# Sheet1.net
KiCad netlist of a schematic drawn in Altium Designer
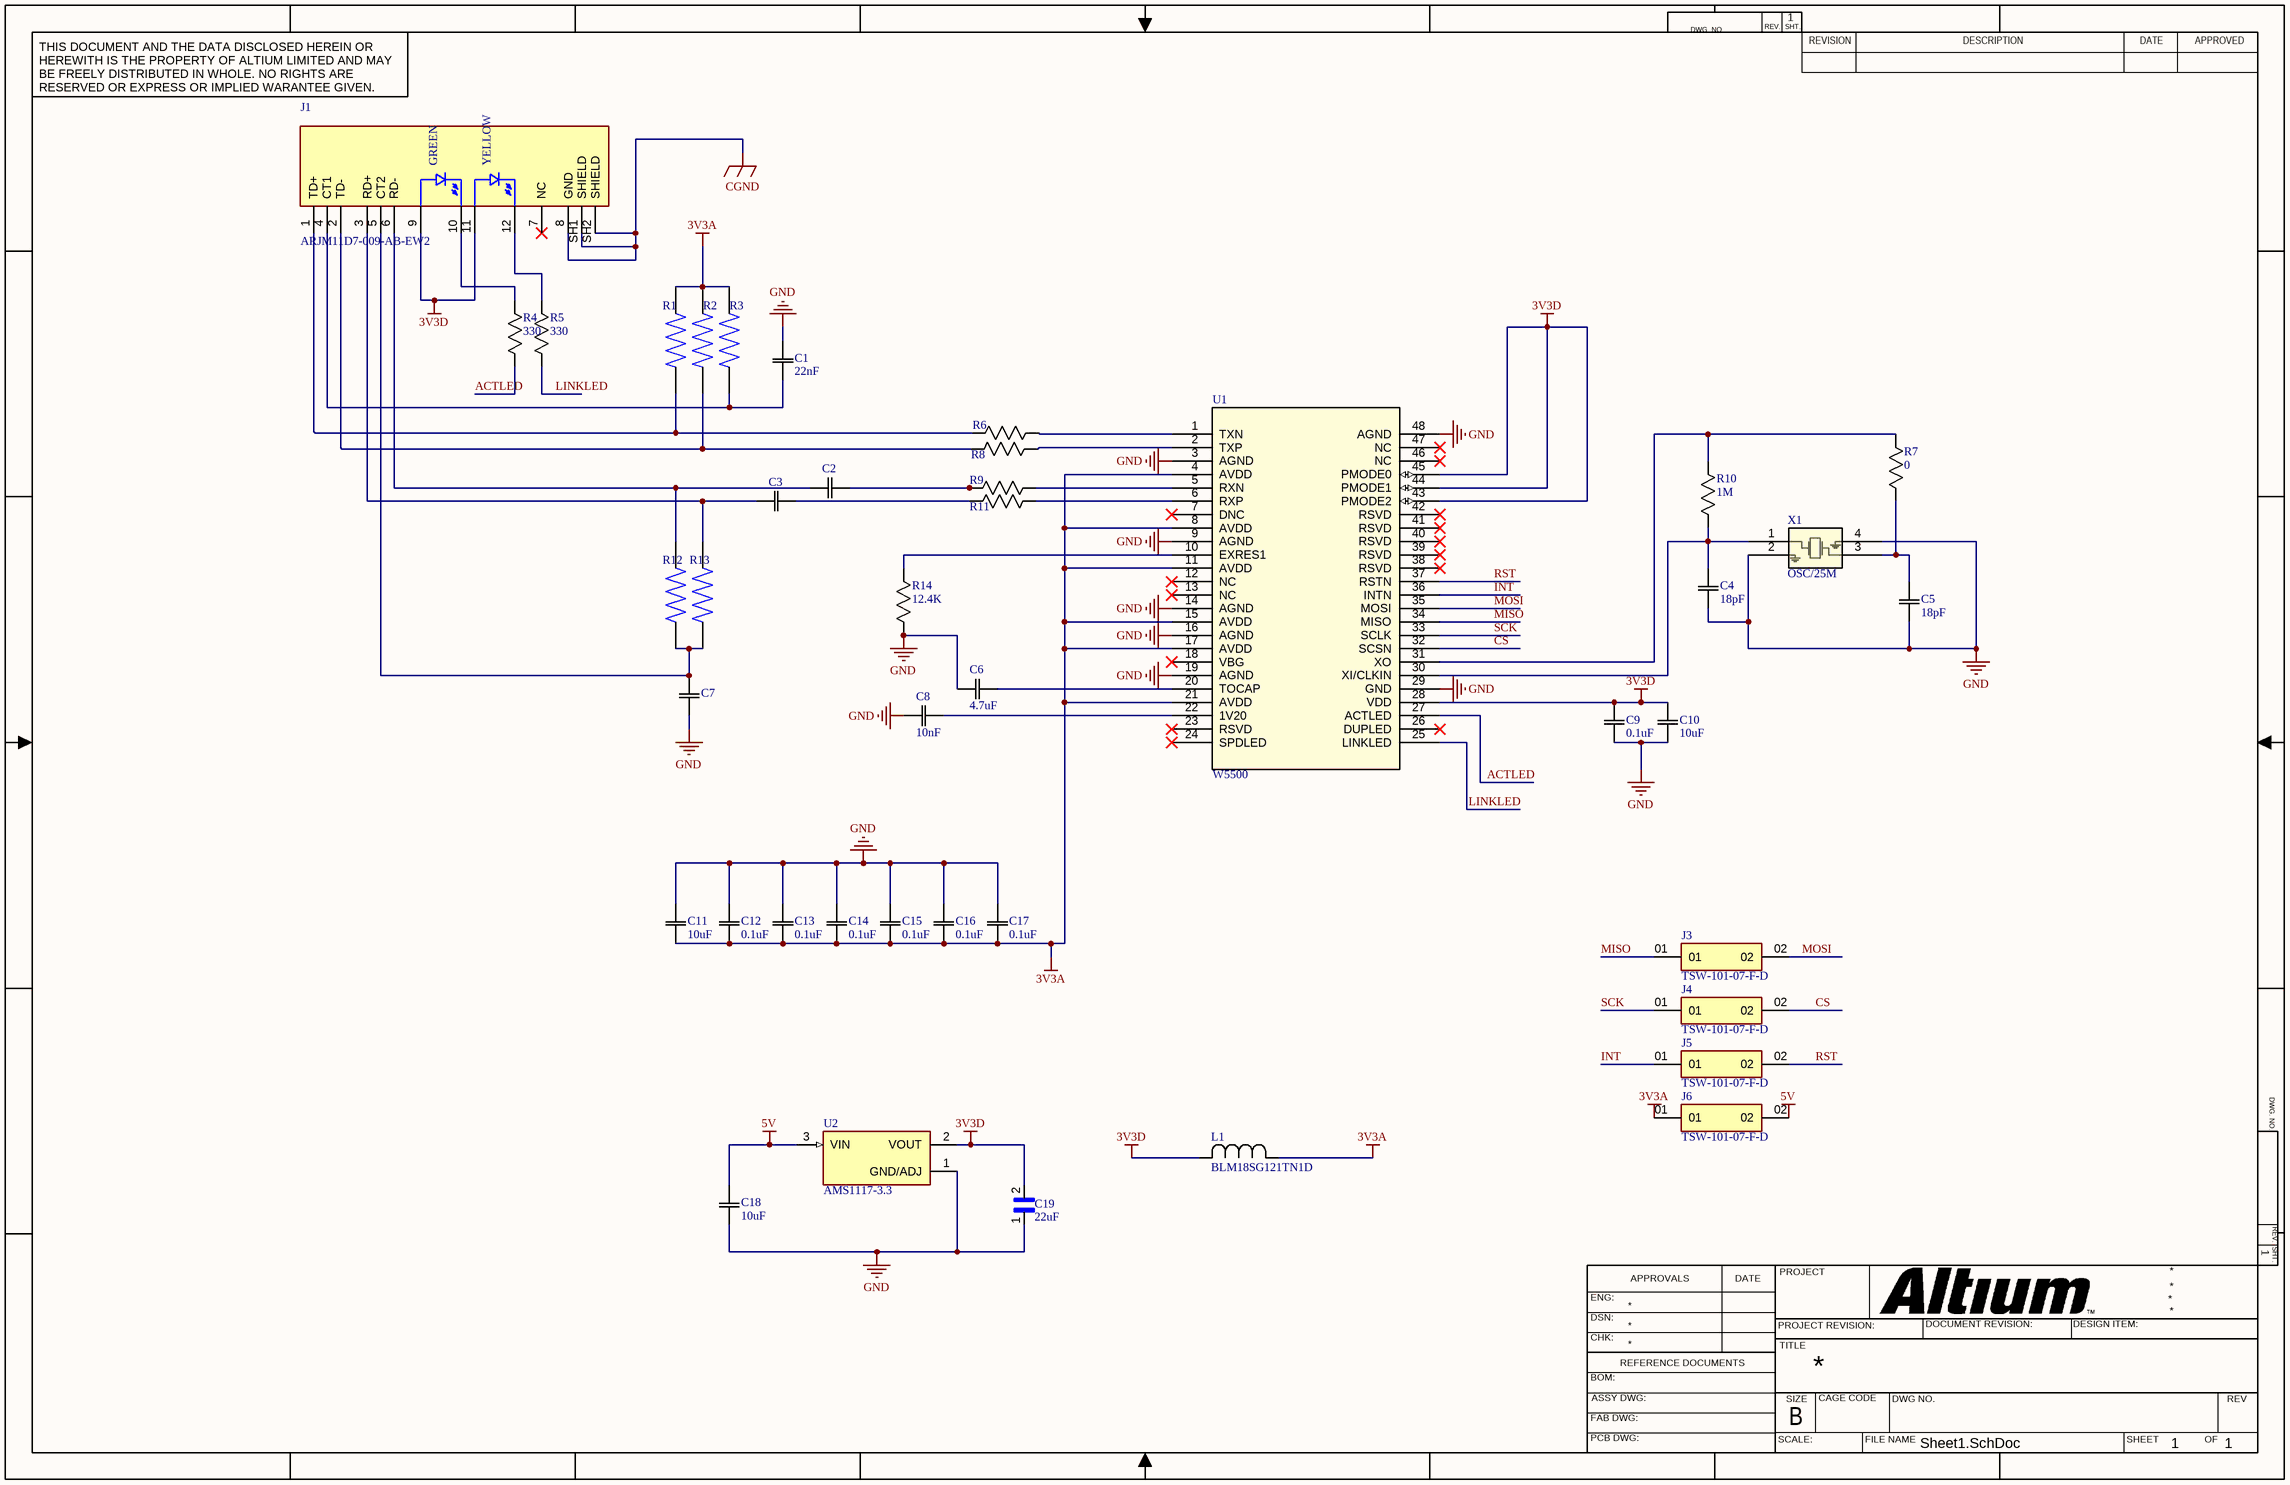
[diagram p0: Sheet1.SchDoc]

(export (version "E")
  (design (tool "Eeschema 10.0.6"))
  (components
    (comp (ref "C1")
      (value "22nF")
      (footprint "CAP_2012_TDK")
      (description "No Description Available")
      (libsource (lib "CAP_22nfar_805pkg") (part "CAP_22nfar_805pkg"))
    )
    (comp (ref "C2")
      (value "CAP_6.8nfar_805pkg")
      (footprint "CC0805N_YAG")
      (description "No Description Available")
      (libsource (lib "CAP_6.8nfar_805pkg") (part "CAP_6.8nfar_805pkg"))
    )
    (comp (ref "C3")
      (value "CAP_6.8nfar_805pkg")
      (footprint "CC0805N_YAG")
      (description "No Description Available")
      (libsource (lib "CAP_6.8nfar_805pkg") (part "CAP_6.8nfar_805pkg"))
    )
    (comp (ref "C4")
      (value "18pF")
      (footprint "CAP_CC0805_YAG")
      (description "No Description Available")
      (libsource (lib "CAP_18pfar_805pkg") (part "CAP_18pfar_805pkg"))
    )
    (comp (ref "C5")
      (value "18pF")
      (footprint "CAP_CC0805_YAG")
      (description "No Description Available")
      (libsource (lib "CAP_18pfar_805pkg") (part "CAP_18pfar_805pkg"))
    )
    (comp (ref "C6")
      (value "4.7uF")
      (footprint "CAP_CL21_SAM")
      (description "No Description Available")
      (libsource (lib "CAP_4.7ufar_805pkg") (part "CAP_4.7ufar_805pkg"))
    )
    (comp (ref "C7")
      (value "CAP_10nfar_805pkg")
      (footprint "CAP_CL21_SAM")
      (description "No Description Available")
      (libsource (lib "CAP_10nfar_805pkg") (part "CAP_10nfar_805pkg"))
    )
    (comp (ref "C8")
      (value "10nF")
      (footprint "CAP_CL21_SAM")
      (description "No Description Available")
      (libsource (lib "CAP_10nfar_805pkg") (part "CAP_10nfar_805pkg"))
    )
    (comp (ref "C9")
      (value "0.1uF")
      (footprint "CC0805N_YAG")
      (description "No Description Available")
      (libsource (lib "CAP_0.1ufar_805pkg") (part "CAP_0.1ufar_805pkg"))
    )
    (comp (ref "C10")
      (value "10uF")
      (footprint "CAP_CL21_SAM")
      (description "No Description Available")
      (libsource (lib "CAP_10ufar_805pkg") (part "CAP_10ufar_805pkg"))
    )
    (comp (ref "C11")
      (value "10uF")
      (footprint "CAP_CL21_SAM")
      (description "No Description Available")
      (libsource (lib "CAP_10ufar_805pkg") (part "CAP_10ufar_805pkg"))
    )
    (comp (ref "C12")
      (value "0.1uF")
      (footprint "CC0805N_YAG")
      (description "No Description Available")
      (libsource (lib "CAP_0.1ufar_805pkg") (part "CAP_0.1ufar_805pkg"))
    )
    (comp (ref "C13")
      (value "0.1uF")
      (footprint "CC0805N_YAG")
      (description "No Description Available")
      (libsource (lib "CAP_0.1ufar_805pkg") (part "CAP_0.1ufar_805pkg"))
    )
    (comp (ref "C14")
      (value "0.1uF")
      (footprint "CC0805N_YAG")
      (description "No Description Available")
      (libsource (lib "CAP_0.1ufar_805pkg") (part "CAP_0.1ufar_805pkg"))
    )
    (comp (ref "C15")
      (value "0.1uF")
      (footprint "CC0805N_YAG")
      (description "No Description Available")
      (libsource (lib "CAP_0.1ufar_805pkg") (part "CAP_0.1ufar_805pkg"))
    )
    (comp (ref "C16")
      (value "0.1uF")
      (footprint "CC0805N_YAG")
      (description "No Description Available")
      (libsource (lib "CAP_0.1ufar_805pkg") (part "CAP_0.1ufar_805pkg"))
    )
    (comp (ref "C17")
      (value "0.1uF")
      (footprint "CC0805N_YAG")
      (description "No Description Available")
      (libsource (lib "CAP_0.1ufar_805pkg") (part "CAP_0.1ufar_805pkg"))
    )
    (comp (ref "C18")
      (value "10uF")
      (footprint "CAP_CL21_SAM")
      (description "No Description Available")
      (libsource (lib "CAP_10ufar_805pkg") (part "CAP_10ufar_805pkg"))
    )
    (comp (ref "C19")
      (value "22uF")
      (footprint "CAPC3225X280N")
      (description "SMD Capacitor X7R_EIA_ with Capacitance: 22uF Tol. 10%. Rated Voltage: 16Vdc")
      (fields (field (name "MP") "GCJ32ER71C226KE01L") (field (name "MF") "Murata"))
      (libsource (lib "CAP_22ufar_1210pkg") (part "GCJ32ER71C226KE01L"))
    )
    (comp (ref "J1")
      (value "ARJM11D7-009-AB-EW2")
      (footprint "ABRACON_ARJM11D7-009-AB-EW2")
      (fields (field (name "MF") "{'manufacturer': u'Abracon LLC'}"))
      (libsource (lib "ARJM11D7-009-AB-EW2") (part "ARJM11D7-009-AB-EW2"))
    )
    (comp (ref "J3")
      (value "TSW-101-07-F-D")
      (footprint "SAMTEC_TSW-101-07-F-D:SAMTEC_TSW-101-07-F-D")
      (fields (field (name "MF") "Samtec"))
      (libsource (lib "TSW-101-07-F-D") (part "TSW-101-07-F-D"))
    )
    (comp (ref "J4")
      (value "TSW-101-07-F-D")
      (footprint "SAMTEC_TSW-101-07-F-D:SAMTEC_TSW-101-07-F-D")
      (fields (field (name "MF") "Samtec"))
      (libsource (lib "TSW-101-07-F-D") (part "TSW-101-07-F-D"))
    )
    (comp (ref "J5")
      (value "TSW-101-07-F-D")
      (footprint "SAMTEC_TSW-101-07-F-D:SAMTEC_TSW-101-07-F-D")
      (fields (field (name "MF") "Samtec"))
      (libsource (lib "TSW-101-07-F-D") (part "TSW-101-07-F-D"))
    )
    (comp (ref "J6")
      (value "TSW-101-07-F-D")
      (footprint "SAMTEC_TSW-101-07-F-D:SAMTEC_TSW-101-07-F-D")
      (fields (field (name "MF") "Samtec"))
      (libsource (lib "TSW-101-07-F-D") (part "TSW-101-07-F-D"))
    )
    (comp (ref "L1")
      (value "BLM18SG121TN1D")
      (footprint "IND_BLM18_0603_MUR")
      (description "No Description Available")
      (libsource (lib "BLM18SG121TN1D") (part "BLM18SG121TN1D"))
    )
    (comp (ref "R1")
      (value "RES_49.9ohm_805pkg")
      (footprint "RESC2012X60N")
      (description "49.9 Ohms Â±1% 0.125W, 1/8W Chip Resistor 0805 _2012 Metric_ Thick Film")
      (fields (field (name "MP") "CRCW080549R9FKEAC") (field (name "MF") "Vishay"))
      (libsource (lib "RES_49.9ohm_806pkg") (part "RES_49.9ohm_805pkg"))
    )
    (comp (ref "R2")
      (value "RES_49.9ohm_805pkg")
      (footprint "RESC2012X60N")
      (description "49.9 Ohms Â±1% 0.125W, 1/8W Chip Resistor 0805 _2012 Metric_ Thick Film")
      (fields (field (name "MP") "CRCW080549R9FKEAC") (field (name "MF") "Vishay"))
      (libsource (lib "RES_49.9ohm_806pkg") (part "RES_49.9ohm_805pkg"))
    )
    (comp (ref "R3")
      (value "RES_49.9ohm_805pkg")
      (footprint "RESC2012X60N")
      (description "49.9 Ohms Â±1% 0.125W, 1/8W Chip Resistor 0805 _2012 Metric_ Thick Film")
      (fields (field (name "MP") "CRCW080549R9FKEAC") (field (name "MF") "Vishay"))
      (libsource (lib "RES_49.9ohm_806pkg") (part "RES_49.9ohm_805pkg"))
    )
    (comp (ref "R4")
      (value "330")
      (footprint "RES_CRCW_0805_VIS")
      (description "No Description Available")
      (libsource (lib "RES_330ohm_805pkg") (part "RES_330ohm_805pkg"))
    )
    (comp (ref "R5")
      (value "330")
      (footprint "RES_CRCW_0805_VIS")
      (description "No Description Available")
      (libsource (lib "RES_330ohm_805pkg") (part "RES_330ohm_805pkg"))
    )
    (comp (ref "R6")
      (value "RES_0ohm_805pkg")
      (footprint "RES_CRCW_0805_VIS")
      (description "No Description Available")
      (libsource (lib "RES_0ohm_805pkg") (part "RES_0ohm_805pkg"))
    )
    (comp (ref "R7")
      (value "0")
      (footprint "RES_CRCW_0805_VIS")
      (description "No Description Available")
      (libsource (lib "RES_0ohm_805pkg") (part "RES_0ohm_805pkg"))
    )
    (comp (ref "R8")
      (value "RES_0ohm_805pkg")
      (footprint "RES_CRCW_0805_VIS")
      (description "No Description Available")
      (libsource (lib "RES_0ohm_805pkg") (part "RES_0ohm_805pkg"))
    )
    (comp (ref "R9")
      (value "RES_0ohm_805pkg")
      (footprint "RES_CRCW_0805_VIS")
      (description "No Description Available")
      (libsource (lib "RES_0ohm_805pkg") (part "RES_0ohm_805pkg"))
    )
    (comp (ref "R10")
      (value "1M")
      (footprint "RES_CRCW_0805")
      (description "No Description Available")
      (libsource (lib "RES_1Mohm_805pkg") (part "RES_1Mohm_805pkg"))
    )
    (comp (ref "R11")
      (value "RES_0ohm_805pkg")
      (footprint "RES_CRCW_0805_VIS")
      (description "No Description Available")
      (libsource (lib "RES_0ohm_805pkg") (part "RES_0ohm_805pkg"))
    )
    (comp (ref "R12")
      (value "RES_49.9ohm_805pkg")
      (footprint "RESC2012X60N")
      (description "49.9 Ohms Â±1% 0.125W, 1/8W Chip Resistor 0805 _2012 Metric_ Thick Film")
      (fields (field (name "MP") "CRCW080549R9FKEAC") (field (name "MF") "Vishay"))
      (libsource (lib "RES_49.9ohm_806pkg") (part "RES_49.9ohm_805pkg"))
    )
    (comp (ref "R13")
      (value "RES_49.9ohm_805pkg")
      (footprint "RESC2012X60N")
      (description "49.9 Ohms Â±1% 0.125W, 1/8W Chip Resistor 0805 _2012 Metric_ Thick Film")
      (fields (field (name "MP") "CRCW080549R9FKEAC") (field (name "MF") "Vishay"))
      (libsource (lib "RES_49.9ohm_806pkg") (part "RES_49.9ohm_805pkg"))
    )
    (comp (ref "R14")
      (value "12.4K")
      (footprint "RES_CRCW_0805")
      (description "No Description Available")
      (libsource (lib "RES_12.4Kohm_805pkg") (part "RES_12.4Kohm_805pkg"))
    )
    (comp (ref "U1")
      (value "W5500")
      (footprint "48LQFP_W5500_WIZ")
      (description "No Description Available")
      (libsource (lib "W5500") (part "W5500"))
    )
    (comp (ref "U2")
      (value "AMS1117-3.3")
      (footprint "SOT229P700X180-4N")
      (description "Sot223/Pkg 1-Amp 3.3-Volt Low Drop Out Voltage Regulatator")
      (fields (field (name "MF") "Advanced Monolithic Systems"))
      (libsource (lib "AMS1117-3.3") (part "AMS1117-3.3"))
    )
    (comp (ref "X1")
      (value "OSC/25M")
      (footprint "ABM8G_ABR")
      (description "No Description Available")
      (libsource (lib "ABM8G-25P000MHZ-4Y-T3") (part "ABM8G-25.000MHZ-4Y-T3"))
    )
  )
  (nets
    (net (code "1") (name "/ACTLED") (class "Default")
      (node (ref "R4") (pin "1") (pinfunction "1_1") (pintype "passive"))
      (node (ref "U1") (pin "27") (pinfunction "ACTLED_27") (pintype "passive"))
    )
    (net (code "2") (name "/CS") (class "Default")
      (node (ref "J4") (pin "02") (pinfunction "02_02") (pintype "passive"))
      (node (ref "U1") (pin "32") (pinfunction "SCSN_32") (pintype "passive"))
    )
    (net (code "3") (name "/INT") (class "Default")
      (node (ref "J5") (pin "01") (pinfunction "01_01") (pintype "passive"))
      (node (ref "U1") (pin "36") (pinfunction "INTN_36") (pintype "passive"))
    )
    (net (code "4") (name "/LINKLED") (class "Default")
      (node (ref "R5") (pin "1") (pinfunction "1_1") (pintype "passive"))
      (node (ref "U1") (pin "25") (pinfunction "LINKLED_25") (pintype "passive"))
    )
    (net (code "5") (name "/MISO") (class "Default")
      (node (ref "J3") (pin "01") (pinfunction "01_01") (pintype "passive"))
      (node (ref "U1") (pin "34") (pinfunction "MISO_34") (pintype "passive"))
    )
    (net (code "6") (name "/MOSI") (class "Default")
      (node (ref "J3") (pin "02") (pinfunction "02_02") (pintype "passive"))
      (node (ref "U1") (pin "35") (pinfunction "MOSI_35") (pintype "passive"))
    )
    (net (code "7") (name "/RST") (class "Default")
      (node (ref "J5") (pin "02") (pinfunction "02_02") (pintype "passive"))
      (node (ref "U1") (pin "37") (pinfunction "RSTN_37") (pintype "passive"))
    )
    (net (code "8") (name "/SCK") (class "Default")
      (node (ref "J4") (pin "01") (pinfunction "01_01") (pintype "passive"))
      (node (ref "U1") (pin "33") (pinfunction "SCLK_33") (pintype "passive"))
    )
    (net (code "9") (name "3V3A") (class "Default")
      (node (ref "C11") (pin "2") (pinfunction "2_2") (pintype "passive"))
      (node (ref "C12") (pin "2") (pinfunction "2_2") (pintype "passive"))
      (node (ref "C13") (pin "2") (pinfunction "2_2") (pintype "passive"))
      (node (ref "C14") (pin "2") (pinfunction "2_2") (pintype "passive"))
      (node (ref "C15") (pin "2") (pinfunction "2_2") (pintype "passive"))
      (node (ref "C16") (pin "2") (pinfunction "2_2") (pintype "passive"))
      (node (ref "C17") (pin "2") (pinfunction "2_2") (pintype "passive"))
      (node (ref "J6") (pin "01") (pinfunction "01_01") (pintype "passive"))
      (node (ref "L1") (pin "1") (pinfunction "1_1") (pintype "passive"))
      (node (ref "R1") (pin "2") (pinfunction "2_2") (pintype "passive"))
      (node (ref "R2") (pin "2") (pinfunction "2_2") (pintype "passive"))
      (node (ref "R3") (pin "2") (pinfunction "2_2") (pintype "passive"))
      (node (ref "U1") (pin "11") (pinfunction "AVDD_11") (pintype "power_in"))
      (node (ref "U1") (pin "15") (pinfunction "AVDD_15") (pintype "power_in"))
      (node (ref "U1") (pin "17") (pinfunction "AVDD_17") (pintype "power_in"))
      (node (ref "U1") (pin "21") (pinfunction "AVDD_21") (pintype "power_in"))
      (node (ref "U1") (pin "4") (pinfunction "AVDD_4") (pintype "power_in"))
      (node (ref "U1") (pin "8") (pinfunction "AVDD_8") (pintype "power_in"))
    )
    (net (code "10") (name "3V3D") (class "Default")
      (node (ref "C10") (pin "1") (pinfunction "1_1") (pintype "passive"))
      (node (ref "C19") (pin "2") (pinfunction "2_2") (pintype "passive"))
      (node (ref "C9") (pin "1") (pinfunction "1_1") (pintype "passive"))
      (node (ref "J1") (pin "11") (pinfunction "11_11") (pintype "passive"))
      (node (ref "J1") (pin "9") (pinfunction "9_9") (pintype "passive"))
      (node (ref "L1") (pin "2") (pinfunction "2_2") (pintype "passive"))
      (node (ref "U1") (pin "28") (pinfunction "VDD_28") (pintype "power_in"))
      (node (ref "U1") (pin "43") (pinfunction "PMODE2_43") (pintype "bidirectional"))
      (node (ref "U1") (pin "44") (pinfunction "PMODE1_44") (pintype "bidirectional"))
      (node (ref "U1") (pin "45") (pinfunction "PMODE0_45") (pintype "bidirectional"))
      (node (ref "U2") (pin "2") (pinfunction "VOUT_2") (pintype "passive"))
    )
    (net (code "11") (name "5V") (class "Default")
      (node (ref "C18") (pin "2") (pinfunction "2_2") (pintype "passive"))
      (node (ref "J6") (pin "02") (pinfunction "02_02") (pintype "passive"))
      (node (ref "U2") (pin "3") (pinfunction "VIN_3") (pintype "input"))
    )
    (net (code "12") (name "CGND") (class "Default")
      (node (ref "J1") (pin "8") (pinfunction "GND_8") (pintype "power_in"))
      (node (ref "J1") (pin "SH1") (pinfunction "SHIELD_SH1") (pintype "passive"))
      (node (ref "J1") (pin "SH2") (pinfunction "SHIELD_SH2") (pintype "passive"))
    )
    (net (code "13") (name "GND") (class "Default")
      (node (ref "C1") (pin "2") (pinfunction "2_2") (pintype "passive"))
      (node (ref "C10") (pin "2") (pinfunction "2_2") (pintype "passive"))
      (node (ref "C11") (pin "1") (pinfunction "1_1") (pintype "passive"))
      (node (ref "C12") (pin "1") (pinfunction "1_1") (pintype "passive"))
      (node (ref "C13") (pin "1") (pinfunction "1_1") (pintype "passive"))
      (node (ref "C14") (pin "1") (pinfunction "1_1") (pintype "passive"))
      (node (ref "C15") (pin "1") (pinfunction "1_1") (pintype "passive"))
      (node (ref "C16") (pin "1") (pinfunction "1_1") (pintype "passive"))
      (node (ref "C17") (pin "1") (pinfunction "1_1") (pintype "passive"))
      (node (ref "C18") (pin "1") (pinfunction "1_1") (pintype "passive"))
      (node (ref "C19") (pin "1") (pinfunction "1_1") (pintype "passive"))
      (node (ref "C4") (pin "1") (pinfunction "1_1") (pintype "passive"))
      (node (ref "C5") (pin "1") (pinfunction "1_1") (pintype "passive"))
      (node (ref "C6") (pin "1") (pinfunction "1_1") (pintype "passive"))
      (node (ref "C7") (pin "1") (pinfunction "1_1") (pintype "passive"))
      (node (ref "C8") (pin "1") (pinfunction "1_1") (pintype "passive"))
      (node (ref "C9") (pin "2") (pinfunction "2_2") (pintype "passive"))
      (node (ref "R14") (pin "2") (pinfunction "2_2") (pintype "passive"))
      (node (ref "U1") (pin "14") (pinfunction "AGND_14") (pintype "power_in"))
      (node (ref "U1") (pin "16") (pinfunction "AGND_16") (pintype "power_in"))
      (node (ref "U1") (pin "19") (pinfunction "AGND_19") (pintype "power_in"))
      (node (ref "U1") (pin "29") (pinfunction "GND_29") (pintype "power_in"))
      (node (ref "U1") (pin "3") (pinfunction "AGND_3") (pintype "power_in"))
      (node (ref "U1") (pin "48") (pinfunction "AGND_48") (pintype "power_in"))
      (node (ref "U1") (pin "9") (pinfunction "AGND_9") (pintype "power_in"))
      (node (ref "U2") (pin "1") (pinfunction "GND/ADJ_1") (pintype "power_in"))
      (node (ref "X1") (pin "2") (pinfunction "2_2") (pintype "passive"))
      (node (ref "X1") (pin "4") (pinfunction "4_4") (pintype "passive"))
    )
    (net (code "14") (name "Net-(C2-Pad2)") (class "Default")
      (node (ref "C2") (pin "2") (pinfunction "2_2") (pintype "passive"))
      (node (ref "R9") (pin "2") (pinfunction "2_2") (pintype "passive"))
    )
    (net (code "15") (name "Net-(C3-Pad2)") (class "Default")
      (node (ref "C3") (pin "2") (pinfunction "2_2") (pintype "passive"))
      (node (ref "R11") (pin "2") (pinfunction "2_2") (pintype "passive"))
    )
    (net (code "16") (name "Net-(C5-Pad2)") (class "Default")
      (node (ref "C5") (pin "2") (pinfunction "2_2") (pintype "passive"))
      (node (ref "R7") (pin "2") (pinfunction "2_2") (pintype "passive"))
      (node (ref "X1") (pin "3") (pinfunction "3_3") (pintype "passive"))
    )
    (net (code "17") (name "Net-(J1-CT1)") (class "Default")
      (node (ref "C1") (pin "1") (pinfunction "1_1") (pintype "passive"))
      (node (ref "J1") (pin "4") (pinfunction "CT1_4") (pintype "passive"))
      (node (ref "R3") (pin "1") (pinfunction "1_1") (pintype "passive"))
    )
    (net (code "18") (name "Net-(J1-CT2)") (class "Default")
      (node (ref "C7") (pin "2") (pinfunction "2_2") (pintype "passive"))
      (node (ref "J1") (pin "5") (pinfunction "CT2_5") (pintype "passive"))
      (node (ref "R12") (pin "1") (pinfunction "1_1") (pintype "passive"))
      (node (ref "R13") (pin "1") (pinfunction "1_1") (pintype "passive"))
    )
    (net (code "19") (name "Net-(J1-Pad10)") (class "Default")
      (node (ref "J1") (pin "10") (pinfunction "10_10") (pintype "passive"))
      (node (ref "R4") (pin "2") (pinfunction "2_2") (pintype "passive"))
    )
    (net (code "20") (name "Net-(J1-Pad12)") (class "Default")
      (node (ref "J1") (pin "12") (pinfunction "12_12") (pintype "passive"))
      (node (ref "R5") (pin "2") (pinfunction "2_2") (pintype "passive"))
    )
    (net (code "21") (name "Net-(J1-RD+)") (class "Default")
      (node (ref "C3") (pin "1") (pinfunction "1_1") (pintype "passive"))
      (node (ref "J1") (pin "3") (pinfunction "RD+_3") (pintype "passive"))
      (node (ref "R13") (pin "2") (pinfunction "2_2") (pintype "passive"))
    )
    (net (code "22") (name "Net-(J1-RD-)") (class "Default")
      (node (ref "C2") (pin "1") (pinfunction "1_1") (pintype "passive"))
      (node (ref "J1") (pin "6") (pinfunction "RD-_6") (pintype "passive"))
      (node (ref "R12") (pin "2") (pinfunction "2_2") (pintype "passive"))
    )
    (net (code "23") (name "Net-(J1-TD+)") (class "Default")
      (node (ref "J1") (pin "1") (pinfunction "TD+_1") (pintype "passive"))
      (node (ref "R1") (pin "1") (pinfunction "1_1") (pintype "passive"))
      (node (ref "R6") (pin "2") (pinfunction "2_2") (pintype "passive"))
    )
    (net (code "24") (name "Net-(J1-TD-)") (class "Default")
      (node (ref "J1") (pin "2") (pinfunction "TD-_2") (pintype "passive"))
      (node (ref "R2") (pin "1") (pinfunction "1_1") (pintype "passive"))
      (node (ref "R8") (pin "2") (pinfunction "2_2") (pintype "passive"))
    )
    (net (code "25") (name "Net-(U1-1V20)") (class "Default")
      (node (ref "C8") (pin "2") (pinfunction "2_2") (pintype "passive"))
      (node (ref "U1") (pin "22") (pinfunction "1V20_22") (pintype "passive"))
    )
    (net (code "26") (name "Net-(U1-EXRES1)") (class "Default")
      (node (ref "R14") (pin "1") (pinfunction "1_1") (pintype "passive"))
      (node (ref "U1") (pin "10") (pinfunction "EXRES1_10") (pintype "passive"))
    )
    (net (code "27") (name "Net-(U1-RXN)") (class "Default")
      (node (ref "R9") (pin "1") (pinfunction "1_1") (pintype "passive"))
      (node (ref "U1") (pin "5") (pinfunction "RXN_5") (pintype "passive"))
    )
    (net (code "28") (name "Net-(U1-RXP)") (class "Default")
      (node (ref "R11") (pin "1") (pinfunction "1_1") (pintype "passive"))
      (node (ref "U1") (pin "6") (pinfunction "RXP_6") (pintype "passive"))
    )
    (net (code "29") (name "Net-(U1-TOCAP)") (class "Default")
      (node (ref "C6") (pin "2") (pinfunction "2_2") (pintype "passive"))
      (node (ref "U1") (pin "20") (pinfunction "TOCAP_20") (pintype "passive"))
    )
    (net (code "30") (name "Net-(U1-TXN)") (class "Default")
      (node (ref "R6") (pin "1") (pinfunction "1_1") (pintype "passive"))
      (node (ref "U1") (pin "1") (pinfunction "TXN_1") (pintype "passive"))
    )
    (net (code "31") (name "Net-(U1-TXP)") (class "Default")
      (node (ref "R8") (pin "1") (pinfunction "1_1") (pintype "passive"))
      (node (ref "U1") (pin "2") (pinfunction "TXP_2") (pintype "passive"))
    )
    (net (code "32") (name "Net-(U1-XI{slash}CLKIN)") (class "Default")
      (node (ref "C4") (pin "2") (pinfunction "2_2") (pintype "passive"))
      (node (ref "R10") (pin "2") (pinfunction "2_2") (pintype "passive"))
      (node (ref "U1") (pin "30") (pinfunction "XI/CLKIN_30") (pintype "passive"))
      (node (ref "X1") (pin "1") (pinfunction "1_1") (pintype "passive"))
    )
    (net (code "33") (name "Net-(U1-XO)") (class "Default")
      (node (ref "R10") (pin "1") (pinfunction "1_1") (pintype "passive"))
      (node (ref "R7") (pin "1") (pinfunction "1_1") (pintype "passive"))
      (node (ref "U1") (pin "31") (pinfunction "XO_31") (pintype "passive"))
    )
    (net (code "34") (name "unconnected-(J1-NC-Pad7)") (class "Default")
      (node (ref "J1") (pin "7") (pinfunction "NC_7") (pintype "passive+no_connect"))
    )
    (net (code "35") (name "unconnected-(U1-DNC-Pad7)") (class "Default")
      (node (ref "U1") (pin "7") (pinfunction "DNC_7") (pintype "passive+no_connect"))
    )
    (net (code "36") (name "unconnected-(U1-DUPLED-Pad26)") (class "Default")
      (node (ref "U1") (pin "26") (pinfunction "DUPLED_26") (pintype "passive+no_connect"))
    )
    (net (code "37") (name "unconnected-(U1-NC-Pad12)") (class "Default")
      (node (ref "U1") (pin "12") (pinfunction "NC_12") (pintype "passive+no_connect"))
    )
    (net (code "38") (name "unconnected-(U1-NC-Pad13)") (class "Default")
      (node (ref "U1") (pin "13") (pinfunction "NC_13") (pintype "passive+no_connect"))
    )
    (net (code "39") (name "unconnected-(U1-NC-Pad46)") (class "Default")
      (node (ref "U1") (pin "46") (pinfunction "NC_46") (pintype "passive+no_connect"))
    )
    (net (code "40") (name "unconnected-(U1-NC-Pad47)") (class "Default")
      (node (ref "U1") (pin "47") (pinfunction "NC_47") (pintype "passive+no_connect"))
    )
    (net (code "41") (name "unconnected-(U1-RSVD-Pad23)") (class "Default")
      (node (ref "U1") (pin "23") (pinfunction "RSVD_23") (pintype "passive+no_connect"))
    )
    (net (code "42") (name "unconnected-(U1-RSVD-Pad38)") (class "Default")
      (node (ref "U1") (pin "38") (pinfunction "RSVD_38") (pintype "passive+no_connect"))
    )
    (net (code "43") (name "unconnected-(U1-RSVD-Pad39)") (class "Default")
      (node (ref "U1") (pin "39") (pinfunction "RSVD_39") (pintype "passive+no_connect"))
    )
    (net (code "44") (name "unconnected-(U1-RSVD-Pad40)") (class "Default")
      (node (ref "U1") (pin "40") (pinfunction "RSVD_40") (pintype "passive+no_connect"))
    )
    (net (code "45") (name "unconnected-(U1-RSVD-Pad41)") (class "Default")
      (node (ref "U1") (pin "41") (pinfunction "RSVD_41") (pintype "passive+no_connect"))
    )
    (net (code "46") (name "unconnected-(U1-RSVD-Pad42)") (class "Default")
      (node (ref "U1") (pin "42") (pinfunction "RSVD_42") (pintype "passive+no_connect"))
    )
    (net (code "47") (name "unconnected-(U1-SPDLED-Pad24)") (class "Default")
      (node (ref "U1") (pin "24") (pinfunction "SPDLED_24") (pintype "passive+no_connect"))
    )
    (net (code "48") (name "unconnected-(U1-VBG-Pad18)") (class "Default")
      (node (ref "U1") (pin "18") (pinfunction "VBG_18") (pintype "passive+no_connect"))
    )
  )
)
